# transmitter_board_single_panel.net
KiCad netlist of a schematic drawn in EAGLE
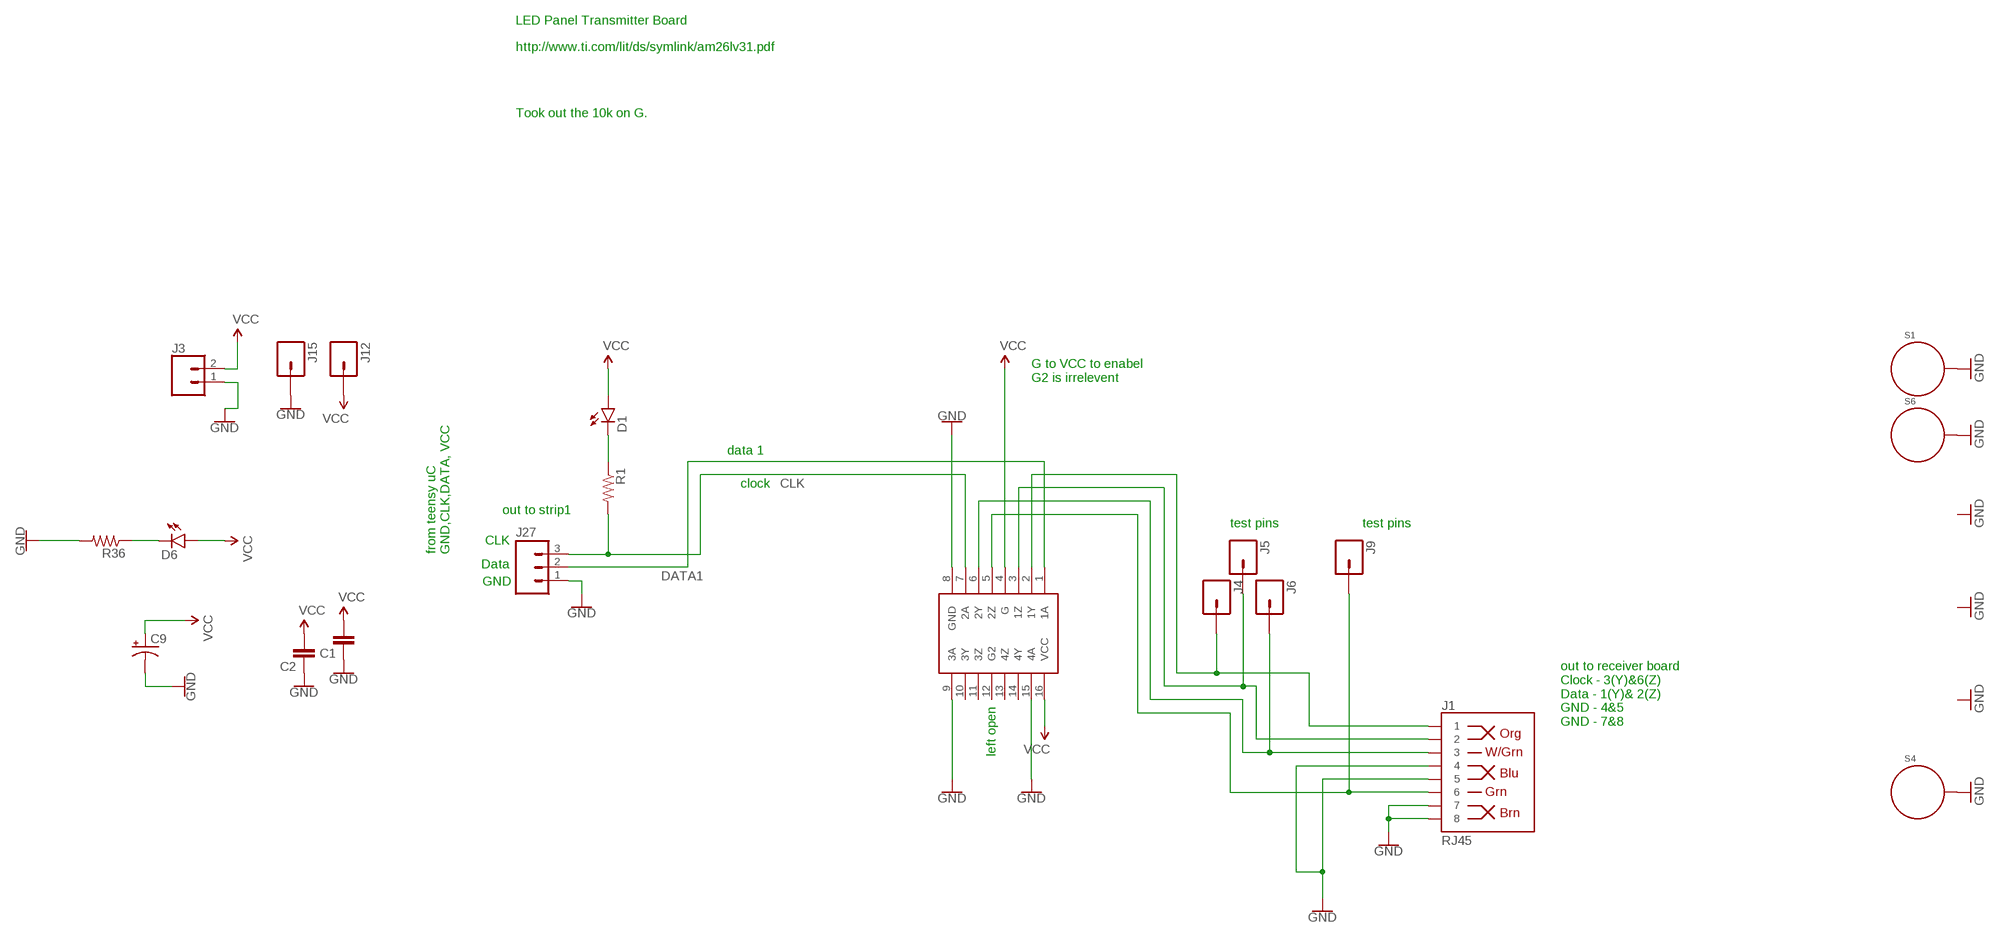
[diagram p0: schematic, sheet 1]

(export (version "E")
  (design (tool "Eeschema 10.0.6"))
  (components
    (comp (ref "C1")
      (value "CAP0805")
      (footprint "eagle-import:0805")
      (libsource (lib "eagle-import") (part "CAP0805"))
    )
    (comp (ref "C2")
      (value "CAP0805")
      (footprint "eagle-import:0805")
      (libsource (lib "eagle-import") (part "CAP0805"))
    )
    (comp (ref "C9")
      (value "CAP_POLPTH1")
      (footprint "eagle-import:CPOL-RADIAL-100UF-25V")
      (libsource (lib "eagle-import") (part "CAP_POLPTH1"))
    )
    (comp (ref "D1")
      (value "LED3MM")
      (footprint "eagle-import:LED3MM")
      (libsource (lib "eagle-import") (part "LED3MM"))
    )
    (comp (ref "D6")
      (value "LED3MM")
      (footprint "eagle-import:LED3MM")
      (libsource (lib "eagle-import") (part "LED3MM"))
    )
    (comp (ref "J1")
      (value "RJ45")
      (footprint "eagle-import:RJ45-8")
      (libsource (lib "eagle-import") (part "RJ45-8"))
    )
    (comp (ref "J3")
      (value "CONN_025MM")
      (footprint "eagle-import:SCREWTERMINAL-5MM-2")
      (libsource (lib "eagle-import") (part "CONN_025MM"))
    )
    (comp (ref "J4")
      (value "M01PTH")
      (footprint "eagle-import:1X01")
      (libsource (lib "eagle-import") (part "M01PTH"))
    )
    (comp (ref "J5")
      (value "M01PTH")
      (footprint "eagle-import:1X01")
      (libsource (lib "eagle-import") (part "M01PTH"))
    )
    (comp (ref "J6")
      (value "M01PTH")
      (footprint "eagle-import:1X01")
      (libsource (lib "eagle-import") (part "M01PTH"))
    )
    (comp (ref "J9")
      (value "M01PTH")
      (footprint "eagle-import:1X01")
      (libsource (lib "eagle-import") (part "M01PTH"))
    )
    (comp (ref "J12")
      (value "M01PTH")
      (footprint "eagle-import:1X01")
      (libsource (lib "eagle-import") (part "M01PTH"))
    )
    (comp (ref "J15")
      (value "M01PTH")
      (footprint "eagle-import:1X01")
      (libsource (lib "eagle-import") (part "M01PTH"))
    )
    (comp (ref "J27")
      (value "M03SCREW")
      (footprint "eagle-import:SCREWTERMINAL-3.5MM-3")
      (libsource (lib "eagle-import") (part "M03SCREW"))
    )
    (comp (ref "R1")
      (value "RESISTOR0805-RES")
      (footprint "eagle-import:0805")
      (libsource (lib "eagle-import") (part "RESISTOR0805-RES"))
    )
    (comp (ref "R36")
      (value "RESISTOR0805-RES")
      (footprint "eagle-import:0805")
      (libsource (lib "eagle-import") (part "RESISTOR0805-RES"))
    )
    (comp (ref "S1")
      (value "STANDOFF_ELECTRICAL5-32")
      (footprint "eagle-import:STANDOFF_ELECTRICAL_5_32")
      (libsource (lib "eagle-import") (part "STANDOFF_ELECTRICAL5-32"))
    )
    (comp (ref "S4")
      (value "STANDOFF_ELECTRICAL5-32")
      (footprint "eagle-import:STANDOFF_ELECTRICAL_5_32")
      (libsource (lib "eagle-import") (part "STANDOFF_ELECTRICAL5-32"))
    )
    (comp (ref "S6")
      (value "STANDOFF_ELECTRICAL5-32")
      (footprint "eagle-import:STANDOFF_ELECTRICAL_5_32")
      (libsource (lib "eagle-import") (part "STANDOFF_ELECTRICAL5-32"))
    )
    (comp (ref "U$1")
      (value "AM26LV31_QUAD_LINE_DRIVER")
      (footprint "eagle-import:SO016")
      (libsource (lib "eagle-import") (part "AM26LV31_QUAD_LINE_DRIVER"))
    )
  )
  (nets
    (net (code "1") (name "/CLK") (class "Default")
      (node (ref "J27") (pin "3") (pinfunction "3_3") (pintype "passive"))
      (node (ref "R1") (pin "2") (pinfunction "2_2") (pintype "passive"))
      (node (ref "U$1") (pin "7") (pinfunction "2A_7") (pintype "bidirectional"))
    )
    (net (code "2") (name "/DATA1") (class "Default")
      (node (ref "J27") (pin "2") (pinfunction "2_2") (pintype "passive"))
      (node (ref "U$1") (pin "1") (pinfunction "1A_1") (pintype "bidirectional"))
    )
    (net (code "3") (name "GND") (class "Default")
      (node (ref "C1") (pin "1") (pinfunction "1_1") (pintype "passive"))
      (node (ref "C2") (pin "1") (pinfunction "1_1") (pintype "passive"))
      (node (ref "C9") (pin "2") (pinfunction "-_2") (pintype "passive"))
      (node (ref "J1") (pin "4") (pinfunction "4_4") (pintype "bidirectional"))
      (node (ref "J1") (pin "5") (pinfunction "5_5") (pintype "bidirectional"))
      (node (ref "J1") (pin "7") (pinfunction "7_7") (pintype "bidirectional"))
      (node (ref "J1") (pin "8") (pinfunction "8_8") (pintype "bidirectional"))
      (node (ref "J15") (pin "1") (pinfunction "1_1") (pintype "passive"))
      (node (ref "J27") (pin "1") (pinfunction "1_1") (pintype "passive"))
      (node (ref "J3") (pin "1") (pinfunction "1_1") (pintype "passive"))
      (node (ref "R36") (pin "2") (pinfunction "2_2") (pintype "passive"))
      (node (ref "S1") (pin "P1") (pinfunction "P$1_P1") (pintype "bidirectional"))
      (node (ref "S4") (pin "P1") (pinfunction "P$1_P1") (pintype "bidirectional"))
      (node (ref "S6") (pin "P1") (pinfunction "P$1_P1") (pintype "bidirectional"))
      (node (ref "U$1") (pin "15") (pinfunction "4A_15") (pintype "bidirectional"))
      (node (ref "U$1") (pin "8") (pinfunction "GND_8") (pintype "bidirectional"))
      (node (ref "U$1") (pin "9") (pinfunction "3A_9") (pintype "bidirectional"))
    )
    (net (code "4") (name "Net-(D1-C)") (class "Default")
      (node (ref "D1") (pin "K") (pinfunction "C_K") (pintype "passive"))
      (node (ref "R1") (pin "1") (pinfunction "1_1") (pintype "passive"))
    )
    (net (code "5") (name "Net-(D6-C)") (class "Default")
      (node (ref "D6") (pin "K") (pinfunction "C_K") (pintype "passive"))
      (node (ref "R36") (pin "1") (pinfunction "1_1") (pintype "passive"))
    )
    (net (code "6") (name "Net-(U$1-1Y)") (class "Default")
      (node (ref "J1") (pin "1") (pinfunction "1_1") (pintype "bidirectional"))
      (node (ref "J4") (pin "1") (pinfunction "1_1") (pintype "passive"))
      (node (ref "U$1") (pin "2") (pinfunction "1Y_2") (pintype "bidirectional"))
    )
    (net (code "7") (name "Net-(U$1-1Z)") (class "Default")
      (node (ref "J1") (pin "2") (pinfunction "2_2") (pintype "bidirectional"))
      (node (ref "J5") (pin "1") (pinfunction "1_1") (pintype "passive"))
      (node (ref "U$1") (pin "3") (pinfunction "1Z_3") (pintype "bidirectional"))
    )
    (net (code "8") (name "Net-(U$1-2Y)") (class "Default")
      (node (ref "J1") (pin "3") (pinfunction "3_3") (pintype "bidirectional"))
      (node (ref "J6") (pin "1") (pinfunction "1_1") (pintype "passive"))
      (node (ref "U$1") (pin "6") (pinfunction "2Y_6") (pintype "bidirectional"))
    )
    (net (code "9") (name "Net-(U$1-2Z)") (class "Default")
      (node (ref "J1") (pin "6") (pinfunction "6_6") (pintype "bidirectional"))
      (node (ref "J9") (pin "1") (pinfunction "1_1") (pintype "passive"))
      (node (ref "U$1") (pin "5") (pinfunction "2Z_5") (pintype "bidirectional"))
    )
    (net (code "10") (name "VCC") (class "Default")
      (node (ref "C1") (pin "2") (pinfunction "2_2") (pintype "passive"))
      (node (ref "C2") (pin "2") (pinfunction "2_2") (pintype "passive"))
      (node (ref "C9") (pin "1") (pinfunction "+_1") (pintype "passive"))
      (node (ref "D1") (pin "A") (pinfunction "A_A") (pintype "passive"))
      (node (ref "D6") (pin "A") (pinfunction "A_A") (pintype "passive"))
      (node (ref "J12") (pin "1") (pinfunction "1_1") (pintype "passive"))
      (node (ref "J3") (pin "2") (pinfunction "2_2") (pintype "passive"))
      (node (ref "U$1") (pin "16") (pinfunction "VCC_16") (pintype "bidirectional"))
      (node (ref "U$1") (pin "4") (pinfunction "G_4") (pintype "bidirectional"))
    )
    (net (code "11") (name "unconnected-(U$1-3Y-Pad10)") (class "Default")
      (node (ref "U$1") (pin "10") (pinfunction "3Y_10") (pintype "bidirectional"))
    )
    (net (code "12") (name "unconnected-(U$1-3Z-Pad11)") (class "Default")
      (node (ref "U$1") (pin "11") (pinfunction "3Z_11") (pintype "bidirectional"))
    )
    (net (code "13") (name "unconnected-(U$1-4Y-Pad14)") (class "Default")
      (node (ref "U$1") (pin "14") (pinfunction "4Y_14") (pintype "bidirectional"))
    )
    (net (code "14") (name "unconnected-(U$1-4Z-Pad13)") (class "Default")
      (node (ref "U$1") (pin "13") (pinfunction "4Z_13") (pintype "bidirectional"))
    )
    (net (code "15") (name "unconnected-(U$1-G2-Pad12)") (class "Default")
      (node (ref "U$1") (pin "12") (pinfunction "G2_12") (pintype "bidirectional"))
    )
  )
)
